# Pedalbox.net
KiCad netlist of a schematic drawn in Altium Designer
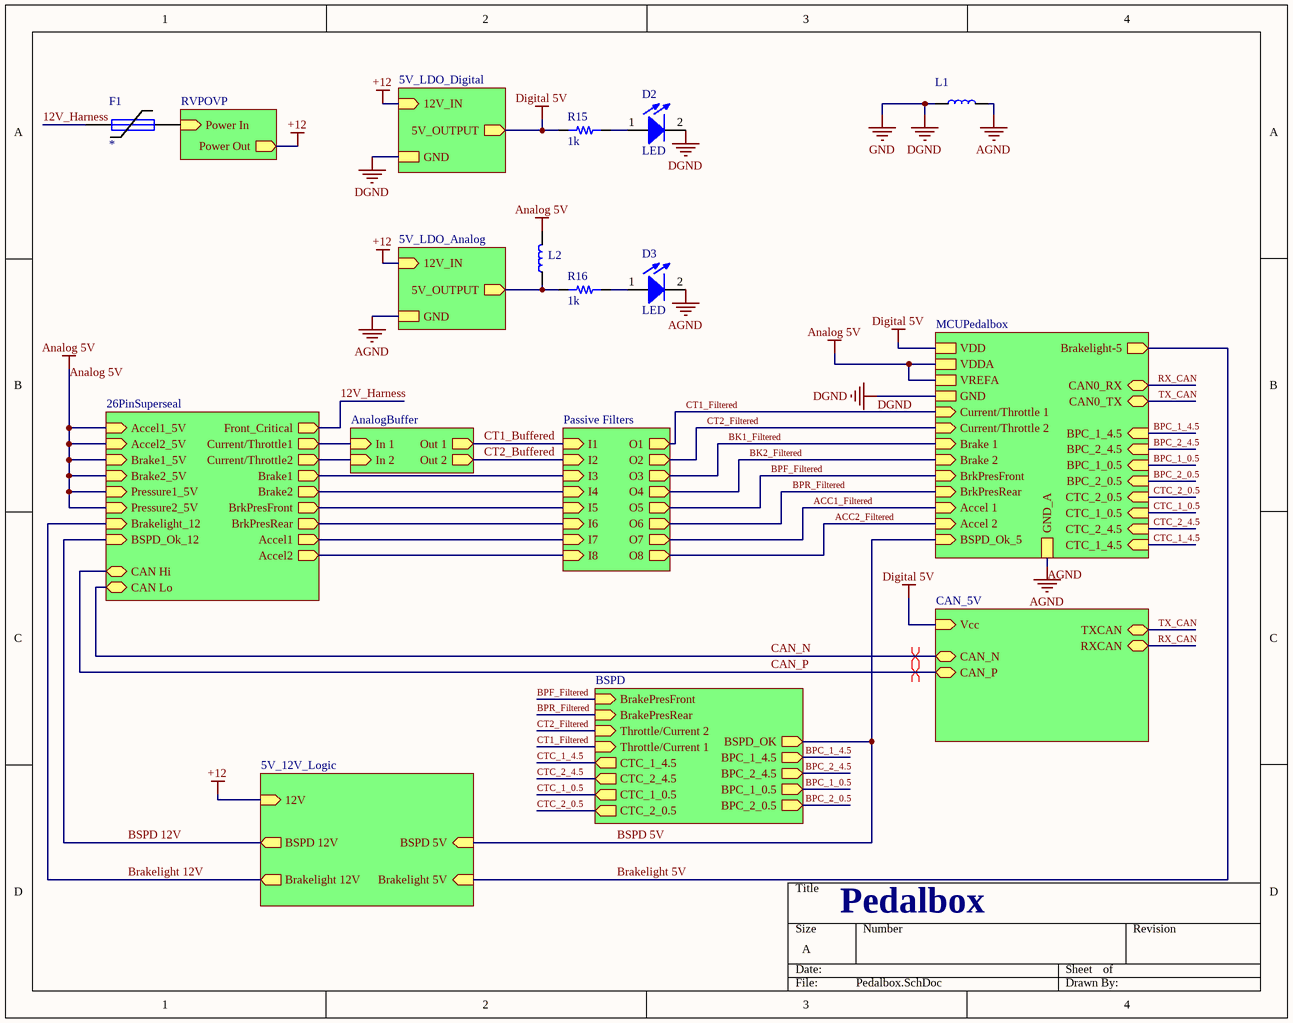
[diagram p0: Pedalbox.SchDoc]

(export (version "E")
  (design (tool "Eeschema 10.0.6"))
  (components
    (comp (ref "D2")
      (value "LED")
      (footprint "0805_LED")
      (description "Generic 0805 LED")
      (libsource (lib "altlib") (part "LED"))
    )
    (comp (ref "D3")
      (value "LED")
      (footprint "0805_LED")
      (description "Generic 0805 LED")
      (libsource (lib "altlib") (part "LED"))
    )
    (comp (ref "F1")
      (value "~")
      (footprint "PTC Fuse 2920/07351")
      (description "Polymeric PTC Resettable Fuse 24V 2A Ih Surfa")
      (fields
        (field (name "I_HOLD") "*")
        (field (name "PUBLISHER") "Altium Limited")
        (field (name "CREATEDBY") "Kevin")
      )
      (libsource (lib "altlib") (part "PTC Fuse"))
    )
    (comp (ref "L1")
      (value "MPZ1608S221ATA00")
      (footprint "0603")
      (description "220 Ohms @ 100MHz 1 Power Line Ferrite Bead 0")
      (fields
        (field (name "DIGI-KEY_PART_NUMBER") "445-1565-1-ND")
        (field (name "MF") "TDK")
        (field (name "CREATEDBY") "Kevin")
      )
      (libsource (lib "altlib") (part "MPZ1608S221ATA00"))
    )
    (comp (ref "L2")
      (value "MPZ1608S221ATA00")
      (footprint "0603")
      (description "220 Ohms @ 100MHz 1 Power Line Ferrite Bead 0")
      (fields
        (field (name "DIGI-KEY_PART_NUMBER") "445-1565-1-ND")
        (field (name "MF") "TDK")
        (field (name "CREATEDBY") "Kevin")
      )
      (libsource (lib "") (part "MPZ1608S221ATA00_1"))
    )
    (comp (ref "R15")
      (value "resistor")
      (footprint "RES 0603/1608")
      (fields (field (name "RESISTANCE") "1k"))
      (libsource (lib "altlib") (part "resistor"))
    )
    (comp (ref "R16")
      (value "resistor")
      (footprint "RES 0603/1608")
      (fields (field (name "RESISTANCE") "1k"))
      (libsource (lib "altlib") (part "resistor"))
    )
  )
  (nets
    (net (code "2") (name "/5V_OUTPUT") (class "Default")
      (node (ref "L2") (pin "1") (pinfunction "1_1") (pintype "passive"))
      (node (ref "R16") (pin "1") (pinfunction "1_1") (pintype "passive"))
    )
    (net (code "3") (name "/12V_Harness") (class "Default")
      (node (ref "F1") (pin "1") (pinfunction "1_1") (pintype "passive"))
    )
    (net (code "36") (name "/Power In") (class "Default")
      (node (ref "F1") (pin "2") (pinfunction "2_2") (pintype "passive"))
    )
    (net (code "39") (name "AGND") (class "Default")
      (node (ref "D3") (pin "2") (pinfunction "K_2") (pintype "passive"))
      (node (ref "L1") (pin "2") (pinfunction "2_2") (pintype "passive"))
    )
    (net (code "40") (name "Analog 5V") (class "Default")
      (node (ref "L2") (pin "2") (pinfunction "2_2") (pintype "passive"))
    )
    (net (code "41") (name "DGND") (class "Default")
      (node (ref "D2") (pin "2") (pinfunction "K_2") (pintype "passive"))
      (node (ref "L1") (pin "1") (pinfunction "1_1") (pintype "passive"))
    )
    (net (code "42") (name "Digital 5V") (class "Default")
      (node (ref "R15") (pin "1") (pinfunction "1_1") (pintype "passive"))
    )
    (net (code "43") (name "Net-(D2-A)") (class "Default")
      (node (ref "D2") (pin "1") (pinfunction "A_1") (pintype "passive"))
      (node (ref "R15") (pin "2") (pinfunction "2_2") (pintype "passive"))
    )
    (net (code "44") (name "Net-(D3-A)") (class "Default")
      (node (ref "D3") (pin "1") (pinfunction "A_1") (pintype "passive"))
      (node (ref "R16") (pin "2") (pinfunction "2_2") (pintype "passive"))
    )
  )
)
